# PROC010B_LP_Connector.net
KiCad netlist of a schematic drawn in Altium Designer
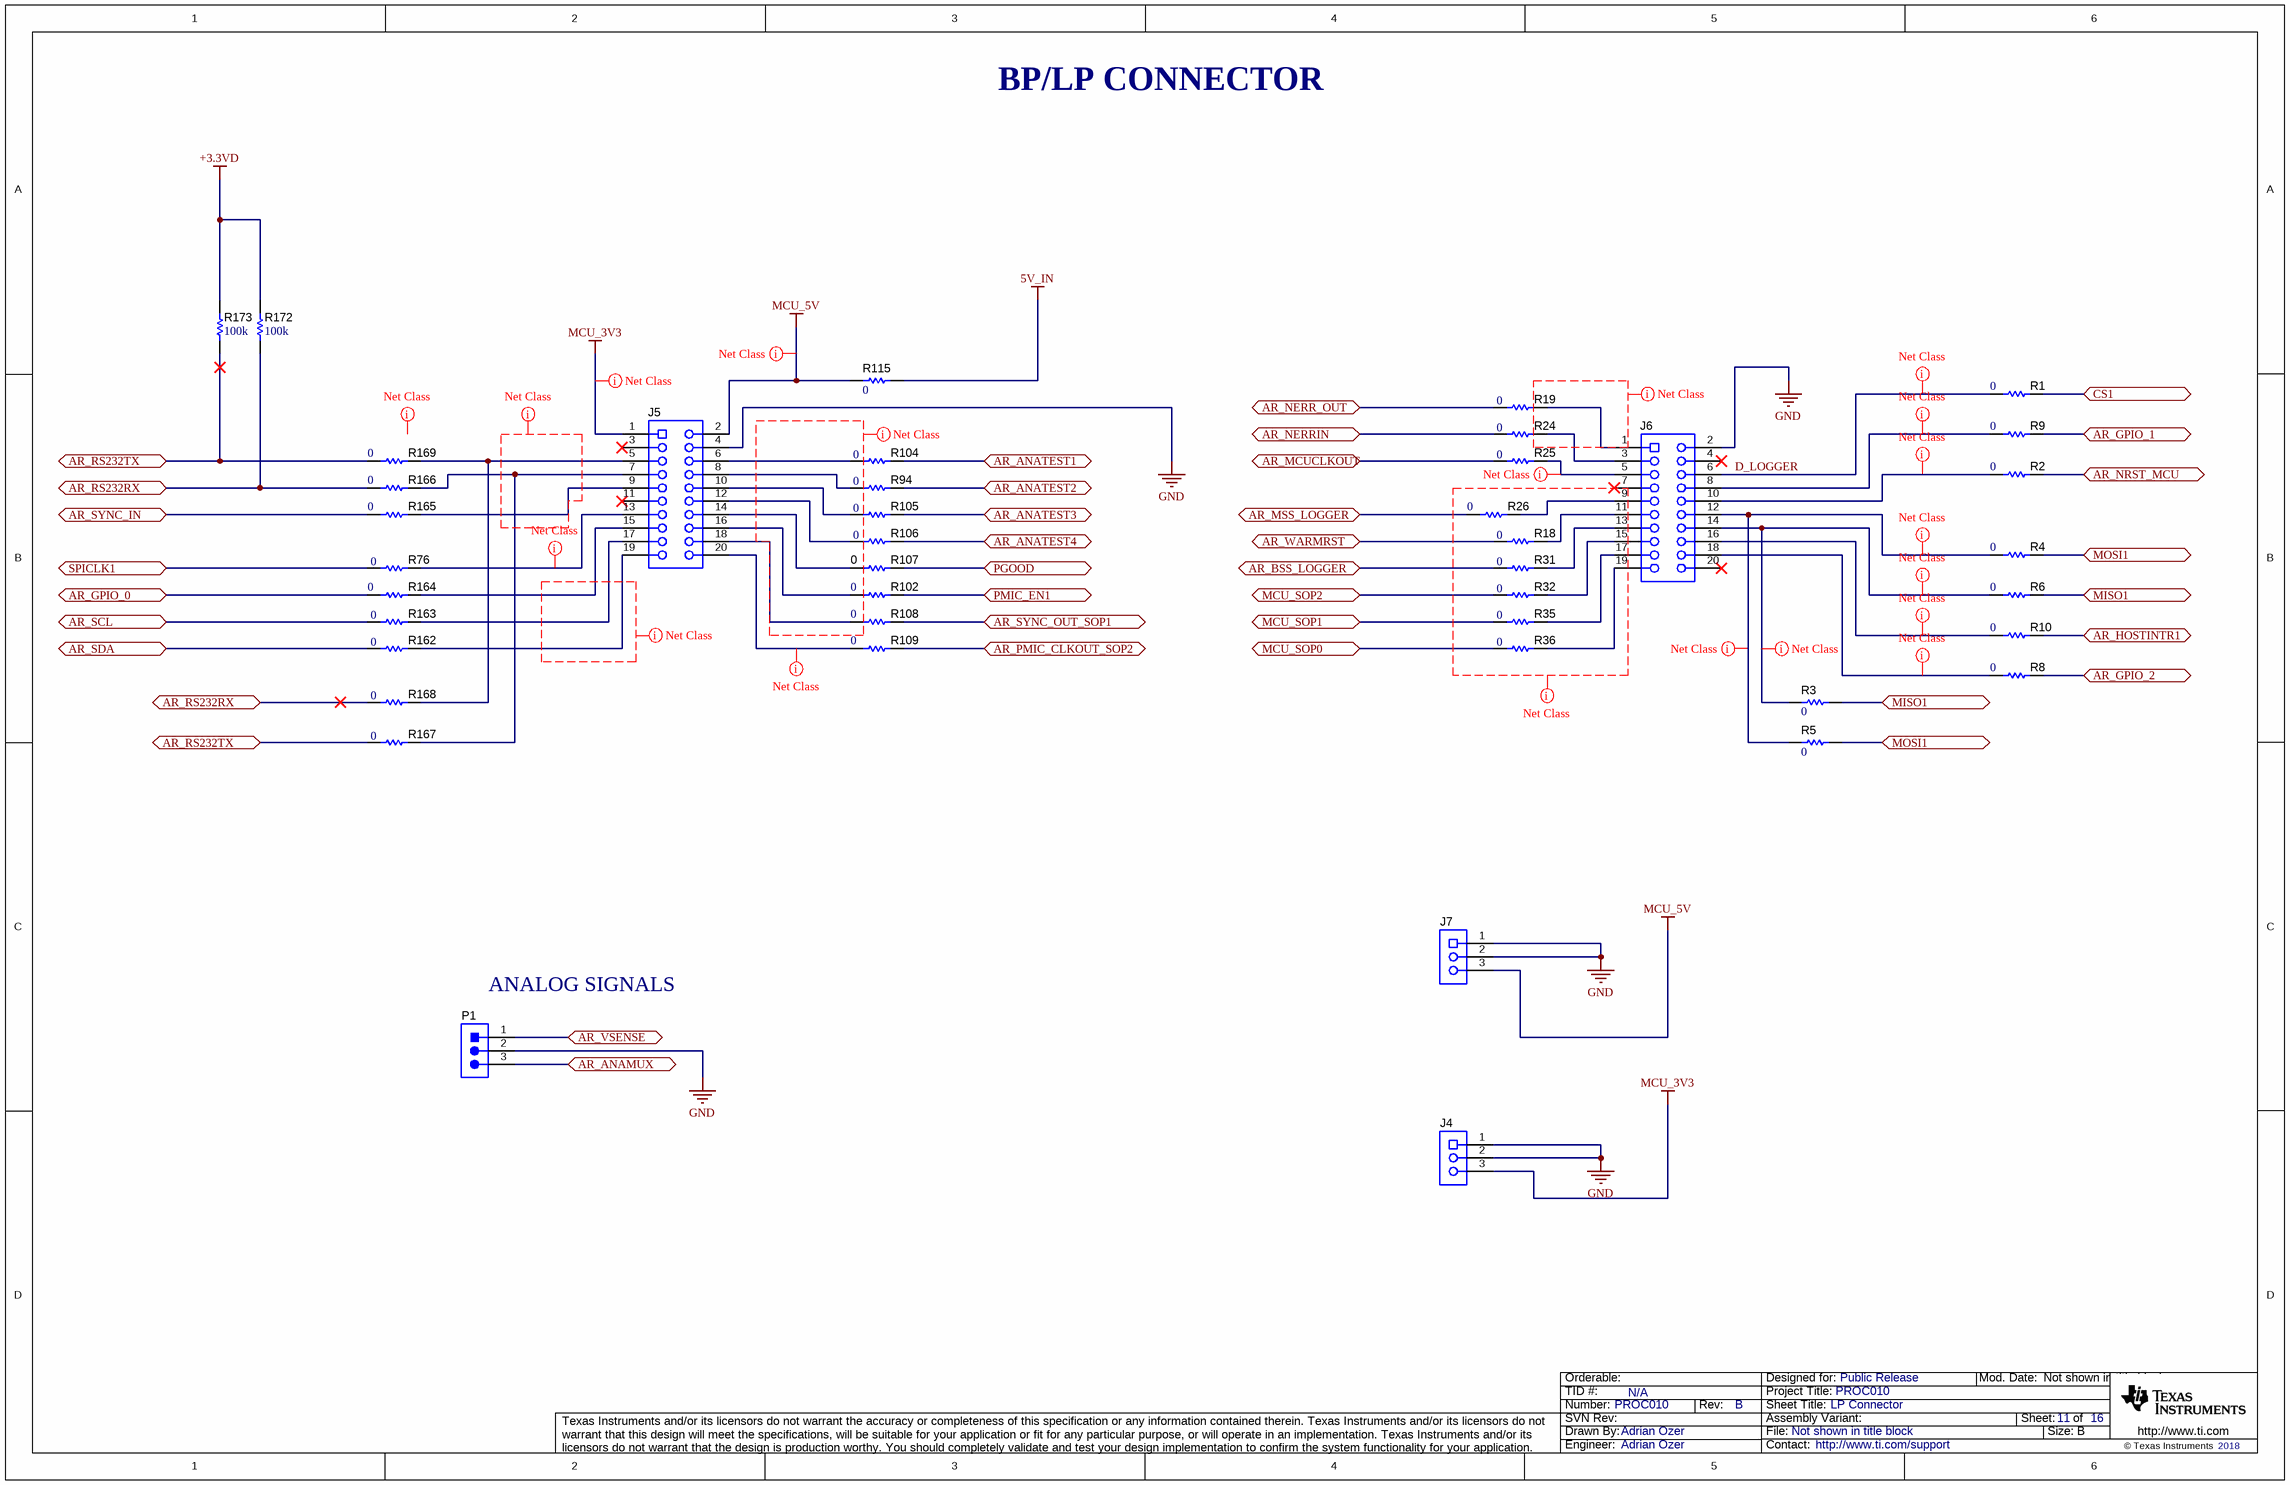
[diagram p0: PROC010B_LP Connector.SchDoc]

(export (version "E")
  (design (tool "Eeschema 10.0.6"))
  (components
    (comp (ref "J4")
      (value "SSM-103-S-SV")
      (footprint "Samtec_SSM-103-x-SV")
      (description "Receptacle, 2.54mm, 3x1, Gold with Tin tail, SMT")
      (fields (field (name "MANUFACTURER") "Samtec"))
      (libsource (lib "Altium Vault - TI") (part "CMP-0078183-1"))
    )
    (comp (ref "J5")
      (value "SSM-110-S-DV")
      (footprint "Samtec_SSM-110-x-DV")
      (description "Receptacle, 2.54mm, 10x2, Gold with Tin tail, SMT")
      (fields (field (name "MANUFACTURER") "Samtec"))
      (libsource (lib "Altium Vault - TI") (part "CMP-0078182-1"))
    )
    (comp (ref "J6")
      (value "SSM-110-S-DV")
      (footprint "Samtec_SSM-110-x-DV")
      (description "Receptacle, 2.54mm, 10x2, Gold with Tin tail, SMT")
      (fields (field (name "MANUFACTURER") "Samtec"))
      (libsource (lib "Altium Vault - TI") (part "CMP-0078182-1"))
    )
    (comp (ref "J7")
      (value "SSM-103-S-SV")
      (footprint "Samtec_SSM-103-x-SV")
      (description "Receptacle, 2.54mm, 3x1, Gold with Tin tail, SMT")
      (fields (field (name "MANUFACTURER") "Samtec"))
      (libsource (lib "Altium Vault - TI") (part "CMP-0078183-1"))
    )
    (comp (ref "P1")
      (value "TSW-103-07-T-S")
      (footprint "Samtec_TSW-103-07-T-S")
      (description "Header, 2.54 mm, 3x1, Tin, TH")
      (fields (field (name "MANUFACTURER") "Samtec"))
      (libsource (lib "Altium Vault - TI") (part "Header_3x1"))
    )
    (comp (ref "R1")
      (value "CRCW02010000Z0ED")
      (footprint "0201_Silk")
      (description "RES, 0, 5%, 0.05 W, 0201")
      (fields (field (name "MANUFACTURER") "Vishay-Dale") (field (name "VALUEDISPLAYED") "0"))
      (libsource (lib "Altium Vault - TI") (part "Resistor"))
    )
    (comp (ref "R2")
      (value "CRCW02010000Z0ED")
      (footprint "0201_Silk")
      (description "RES, 0, 5%, 0.05 W, 0201")
      (fields (field (name "MANUFACTURER") "Vishay-Dale") (field (name "VALUEDISPLAYED") "0"))
      (libsource (lib "Altium Vault - TI") (part "Resistor"))
    )
    (comp (ref "R3")
      (value "CRCW02010000Z0ED")
      (footprint "0201_Silk")
      (description "RES, 0, 5%, 0.05 W, 0201")
      (fields (field (name "MANUFACTURER") "Vishay-Dale") (field (name "VALUEDISPLAYED") "0"))
      (libsource (lib "Altium Vault - TI") (part "Resistor"))
    )
    (comp (ref "R4")
      (value "CRCW02010000Z0ED")
      (footprint "0201_Silk")
      (description "RES, 0, 5%, 0.05 W, 0201")
      (fields (field (name "MANUFACTURER") "Vishay-Dale") (field (name "VALUEDISPLAYED") "0"))
      (libsource (lib "Altium Vault - TI") (part "Resistor"))
    )
    (comp (ref "R5")
      (value "CRCW02010000Z0ED")
      (footprint "0201_Silk")
      (description "RES, 0, 5%, 0.05 W, 0201")
      (fields (field (name "MANUFACTURER") "Vishay-Dale") (field (name "VALUEDISPLAYED") "0"))
      (libsource (lib "Altium Vault - TI") (part "Resistor"))
    )
    (comp (ref "R6")
      (value "CRCW02010000Z0ED")
      (footprint "0201_Silk")
      (description "RES, 0, 5%, 0.05 W, 0201")
      (fields (field (name "MANUFACTURER") "Vishay-Dale") (field (name "VALUEDISPLAYED") "0"))
      (libsource (lib "Altium Vault - TI") (part "Resistor"))
    )
    (comp (ref "R8")
      (value "CRCW02010000Z0ED")
      (footprint "0201_Silk")
      (description "RES, 0, 5%, 0.05 W, 0201")
      (fields (field (name "MANUFACTURER") "Vishay-Dale") (field (name "VALUEDISPLAYED") "0"))
      (libsource (lib "Altium Vault - TI") (part "Resistor"))
    )
    (comp (ref "R9")
      (value "CRCW02010000Z0ED")
      (footprint "0201_Silk")
      (description "RES, 0, 5%, 0.05 W, 0201")
      (fields (field (name "MANUFACTURER") "Vishay-Dale") (field (name "VALUEDISPLAYED") "0"))
      (libsource (lib "Altium Vault - TI") (part "Resistor"))
    )
    (comp (ref "R10")
      (value "CRCW02010000Z0ED")
      (footprint "0201_Silk")
      (description "RES, 0, 5%, 0.05 W, 0201")
      (fields (field (name "MANUFACTURER") "Vishay-Dale") (field (name "VALUEDISPLAYED") "0"))
      (libsource (lib "Altium Vault - TI") (part "Resistor"))
    )
    (comp (ref "R18")
      (value "CRCW02010000Z0ED")
      (footprint "0201_Silk")
      (description "RES, 0, 5%, 0.05 W, 0201")
      (fields (field (name "MANUFACTURER") "Vishay-Dale") (field (name "VALUEDISPLAYED") "0"))
      (libsource (lib "Altium Vault - TI") (part "Resistor"))
    )
    (comp (ref "R19")
      (value "CRCW02010000Z0ED")
      (footprint "0201_Silk")
      (description "RES, 0, 5%, 0.05 W, 0201")
      (fields (field (name "MANUFACTURER") "Vishay-Dale") (field (name "VALUEDISPLAYED") "0"))
      (libsource (lib "Altium Vault - TI") (part "Resistor"))
    )
    (comp (ref "R24")
      (value "CRCW02010000Z0ED")
      (footprint "0201_Silk")
      (description "RES, 0, 5%, 0.05 W, 0201")
      (fields (field (name "MANUFACTURER") "Vishay-Dale") (field (name "VALUEDISPLAYED") "0"))
      (libsource (lib "Altium Vault - TI") (part "Resistor"))
    )
    (comp (ref "R25")
      (value "CRCW02010000Z0ED")
      (footprint "0201_Silk")
      (description "RES, 0, 5%, 0.05 W, 0201")
      (fields (field (name "MANUFACTURER") "Vishay-Dale") (field (name "VALUEDISPLAYED") "0"))
      (libsource (lib "Altium Vault - TI") (part "Resistor"))
    )
    (comp (ref "R26")
      (value "CRCW02010000Z0ED")
      (footprint "0201_Silk")
      (description "RES, 0, 5%, 0.05 W, 0201")
      (fields (field (name "MANUFACTURER") "Vishay-Dale") (field (name "VALUEDISPLAYED") "0"))
      (libsource (lib "Altium Vault - TI") (part "Resistor"))
    )
    (comp (ref "R31")
      (value "CRCW02010000Z0ED")
      (footprint "0201_Silk")
      (description "RES, 0, 5%, 0.05 W, 0201")
      (fields (field (name "MANUFACTURER") "Vishay-Dale") (field (name "VALUEDISPLAYED") "0"))
      (libsource (lib "Altium Vault - TI") (part "Resistor"))
    )
    (comp (ref "R32")
      (value "CRCW02010000Z0ED")
      (footprint "0201_Silk")
      (description "RES, 0, 5%, 0.05 W, 0201")
      (fields (field (name "MANUFACTURER") "Vishay-Dale") (field (name "VALUEDISPLAYED") "0"))
      (libsource (lib "Altium Vault - TI") (part "Resistor"))
    )
    (comp (ref "R35")
      (value "CRCW02010000Z0ED")
      (footprint "0201_Silk")
      (description "RES, 0, 5%, 0.05 W, 0201")
      (fields (field (name "MANUFACTURER") "Vishay-Dale") (field (name "VALUEDISPLAYED") "0"))
      (libsource (lib "Altium Vault - TI") (part "Resistor"))
    )
    (comp (ref "R36")
      (value "CRCW02010000Z0ED")
      (footprint "0201_Silk")
      (description "RES, 0, 5%, 0.05 W, 0201")
      (fields (field (name "MANUFACTURER") "Vishay-Dale") (field (name "VALUEDISPLAYED") "0"))
      (libsource (lib "Altium Vault - TI") (part "Resistor"))
    )
    (comp (ref "R76")
      (value "CRCW02010000Z0ED")
      (footprint "0201_Silk")
      (description "RES, 0, 5%, 0.05 W, 0201")
      (fields (field (name "MANUFACTURER") "Vishay-Dale") (field (name "VALUEDISPLAYED") "0"))
      (libsource (lib "Altium Vault - TI") (part "CMP-0027008-4"))
    )
    (comp (ref "R94")
      (value "CRCW02010000Z0ED")
      (footprint "0201_Silk")
      (description "RES, 0, 5%, 0.05 W, 0201")
      (fields (field (name "MANUFACTURER") "Vishay-Dale") (field (name "VALUEDISPLAYED") "0"))
      (libsource (lib "Altium Vault - TI") (part "Resistor"))
    )
    (comp (ref "R102")
      (value "CRCW02010000Z0ED")
      (footprint "0201_Silk")
      (description "RES, 0, 5%, 0.05 W, 0201")
      (fields (field (name "MANUFACTURER") "Vishay-Dale") (field (name "VALUEDISPLAYED") "0"))
      (libsource (lib "Altium Vault - TI") (part "Resistor"))
    )
    (comp (ref "R104")
      (value "CRCW02010000Z0ED")
      (footprint "0201_Silk")
      (description "RES, 0, 5%, 0.05 W, 0201")
      (fields (field (name "MANUFACTURER") "Vishay-Dale") (field (name "VALUEDISPLAYED") "0"))
      (libsource (lib "Altium Vault - TI") (part "CMP-0027008-4"))
    )
    (comp (ref "R105")
      (value "CRCW02010000Z0ED")
      (footprint "0201_Silk")
      (description "RES, 0, 5%, 0.05 W, 0201")
      (fields (field (name "MANUFACTURER") "Vishay-Dale") (field (name "VALUEDISPLAYED") "0"))
      (libsource (lib "Altium Vault - TI") (part "Resistor"))
    )
    (comp (ref "R106")
      (value "CRCW02010000Z0ED")
      (footprint "0201_Silk")
      (description "RES, 0, 5%, 0.05 W, 0201")
      (fields (field (name "MANUFACTURER") "Vishay-Dale") (field (name "VALUEDISPLAYED") "0"))
      (libsource (lib "Altium Vault - TI") (part "Resistor"))
    )
    (comp (ref "R107")
      (value "ERJ-2GE0R00X")
      (footprint "0402L")
      (description "RES, 0, 5%, 0.063 W, 0402")
      (fields
        (field (name "MANUFACTURER") "Panasonic")
        (field (name "VALUEDISPLAYED") "0")
        (field (name "PUBLISHER") "Texas Instruments")
      )
      (libsource (lib "Altium Vault - TI") (part "Resistor"))
    )
    (comp (ref "R108")
      (value "CRCW02010000Z0ED")
      (footprint "0201_Silk")
      (description "RES, 0, 5%, 0.05 W, 0201")
      (fields (field (name "MANUFACTURER") "Vishay-Dale") (field (name "VALUEDISPLAYED") "0"))
      (libsource (lib "Altium Vault - TI") (part "Resistor"))
    )
    (comp (ref "R109")
      (value "CRCW02010000Z0ED")
      (footprint "0201_Silk")
      (description "RES, 0, 5%, 0.05 W, 0201")
      (fields (field (name "MANUFACTURER") "Vishay-Dale") (field (name "VALUEDISPLAYED") "0"))
      (libsource (lib "Altium Vault - TI") (part "Resistor"))
    )
    (comp (ref "R115")
      (value "CRCW20100000Z0EF")
      (footprint "2010")
      (description "RES, 0, 5%, 0.75 W, AEC-Q200 Grade 0, 2010")
      (fields (field (name "MANUFACTURER") "Vishay-Dale") (field (name "VALUEDISPLAYED") "0"))
      (libsource (lib "Altium Vault - TI") (part "Resistor"))
    )
    (comp (ref "R162")
      (value "CRCW02010000Z0ED")
      (footprint "0201_Silk")
      (description "RES, 0, 5%, 0.05 W, 0201")
      (fields (field (name "MANUFACTURER") "Vishay-Dale") (field (name "VALUEDISPLAYED") "0"))
      (libsource (lib "Altium Vault - TI") (part "Resistor"))
    )
    (comp (ref "R163")
      (value "CRCW02010000Z0ED")
      (footprint "0201_Silk")
      (description "RES, 0, 5%, 0.05 W, 0201")
      (fields (field (name "MANUFACTURER") "Vishay-Dale") (field (name "VALUEDISPLAYED") "0"))
      (libsource (lib "Altium Vault - TI") (part "Resistor"))
    )
    (comp (ref "R164")
      (value "CRCW02010000Z0ED")
      (footprint "0201_Silk")
      (description "RES, 0, 5%, 0.05 W, 0201")
      (fields (field (name "MANUFACTURER") "Vishay-Dale") (field (name "VALUEDISPLAYED") "0"))
      (libsource (lib "Altium Vault - TI") (part "Resistor"))
    )
    (comp (ref "R165")
      (value "CRCW02010000Z0ED")
      (footprint "0201_Silk")
      (description "RES, 0, 5%, 0.05 W, 0201")
      (fields (field (name "MANUFACTURER") "Vishay-Dale") (field (name "VALUEDISPLAYED") "0"))
      (libsource (lib "Altium Vault - TI") (part "Resistor"))
    )
    (comp (ref "R166")
      (value "CRCW02010000Z0ED")
      (footprint "0201_Silk")
      (description "RES, 0, 5%, 0.05 W, 0201")
      (fields (field (name "MANUFACTURER") "Vishay-Dale") (field (name "VALUEDISPLAYED") "0"))
      (libsource (lib "Altium Vault - TI") (part "Resistor"))
    )
    (comp (ref "R167")
      (value "CRCW02010000Z0ED")
      (footprint "0201_Silk")
      (description "RES, 0, 5%, 0.05 W, 0201")
      (fields (field (name "MANUFACTURER") "Vishay-Dale") (field (name "VALUEDISPLAYED") "0"))
      (libsource (lib "Altium Vault - TI") (part "Resistor"))
    )
    (comp (ref "R168")
      (value "CRCW02010000Z0ED")
      (footprint "0201_Silk")
      (description "RES, 0, 5%, 0.05 W, 0201")
      (fields (field (name "MANUFACTURER") "Vishay-Dale") (field (name "VALUEDISPLAYED") "0"))
      (libsource (lib "Altium Vault - TI") (part "Resistor"))
    )
    (comp (ref "R169")
      (value "CRCW02010000Z0ED")
      (footprint "0201_Silk")
      (description "RES, 0, 5%, 0.05 W, 0201")
      (fields (field (name "MANUFACTURER") "Vishay-Dale") (field (name "VALUEDISPLAYED") "0"))
      (libsource (lib "Altium Vault - TI") (part "Resistor"))
    )
    (comp (ref "R172")
      (value "CRCW0402100KFKED")
      (footprint "0402L")
      (description "RES, 100 k, 1%, 0.063 W, AEC-Q200 Grade 0, 0402")
      (fields (field (name "MANUFACTURER") "Vishay-Dale") (field (name "VALUEDISPLAYED") "100k"))
      (libsource (lib "Altium Vault - TI") (part "Resistor"))
    )
    (comp (ref "R173")
      (value "CRCW0402100KFKED")
      (footprint "0402L")
      (description "RES, 100 k, 1%, 0.063 W, AEC-Q200 Grade 0, 0402")
      (fields (field (name "MANUFACTURER") "Vishay-Dale") (field (name "VALUEDISPLAYED") "100k"))
      (libsource (lib "Altium Vault - TI") (part "Resistor"))
    )
  )
  (nets
    (net (code "1") (name "+3.3VD") (class "Default")
      (node (ref "R172") (pin "2") (pinfunction "2_2") (pintype "passive"))
      (node (ref "R173") (pin "2") (pinfunction "2_2") (pintype "passive"))
    )
    (net (code "2") (name "/AR_ANAMUX") (class "Default")
      (node (ref "P1") (pin "3") (pinfunction "3_3") (pintype "passive"))
    )
    (net (code "3") (name "/AR_ANATEST1") (class "Default")
      (node (ref "R104") (pin "2") (pinfunction "2_2") (pintype "passive"))
    )
    (net (code "4") (name "/AR_ANATEST2") (class "Default")
      (node (ref "R94") (pin "2") (pinfunction "2_2") (pintype "passive"))
    )
    (net (code "5") (name "/AR_ANATEST3") (class "Default")
      (node (ref "R105") (pin "2") (pinfunction "2_2") (pintype "passive"))
    )
    (net (code "6") (name "/AR_ANATEST4") (class "Default")
      (node (ref "R106") (pin "2") (pinfunction "2_2") (pintype "passive"))
    )
    (net (code "7") (name "/AR_BSS_LOGGER") (class "Default")
      (node (ref "R31") (pin "1") (pinfunction "1_1") (pintype "passive"))
    )
    (net (code "8") (name "/AR_GPIO_0") (class "Default")
      (node (ref "R164") (pin "1") (pinfunction "1_1") (pintype "passive"))
    )
    (net (code "9") (name "/AR_GPIO_1") (class "Default")
      (node (ref "R9") (pin "2") (pinfunction "2_2") (pintype "passive"))
    )
    (net (code "10") (name "/AR_GPIO_2") (class "Default")
      (node (ref "R8") (pin "2") (pinfunction "2_2") (pintype "passive"))
    )
    (net (code "11") (name "/AR_HOSTINTR1") (class "Default")
      (node (ref "R10") (pin "2") (pinfunction "2_2") (pintype "passive"))
    )
    (net (code "12") (name "/AR_MCUCLKOUT") (class "Default")
      (node (ref "R25") (pin "1") (pinfunction "1_1") (pintype "passive"))
    )
    (net (code "13") (name "/AR_MSS_LOGGER") (class "Default")
      (node (ref "R26") (pin "1") (pinfunction "1_1") (pintype "passive"))
    )
    (net (code "14") (name "/AR_NERRIN") (class "Default")
      (node (ref "R24") (pin "1") (pinfunction "1_1") (pintype "passive"))
    )
    (net (code "15") (name "/AR_NERR_OUT") (class "Default")
      (node (ref "R19") (pin "1") (pinfunction "1_1") (pintype "passive"))
    )
    (net (code "16") (name "/AR_NRST_MCU") (class "Default")
      (node (ref "R2") (pin "2") (pinfunction "2_2") (pintype "passive"))
    )
    (net (code "17") (name "/AR_PMIC_CLKOUT_SOP2") (class "Default")
      (node (ref "R109") (pin "2") (pinfunction "2_2") (pintype "passive"))
    )
    (net (code "18") (name "/AR_RS232RX") (class "Default")
      (node (ref "R166") (pin "1") (pinfunction "1_1") (pintype "passive"))
      (node (ref "R168") (pin "1") (pinfunction "1_1") (pintype "passive"))
      (node (ref "R172") (pin "1") (pinfunction "1_1") (pintype "passive"))
    )
    (net (code "19") (name "/AR_RS232TX") (class "Default")
      (node (ref "R167") (pin "1") (pinfunction "1_1") (pintype "passive"))
      (node (ref "R169") (pin "1") (pinfunction "1_1") (pintype "passive"))
      (node (ref "R173") (pin "1") (pinfunction "1_1") (pintype "passive"))
    )
    (net (code "20") (name "/AR_SCL") (class "Default")
      (node (ref "R163") (pin "1") (pinfunction "1_1") (pintype "passive"))
    )
    (net (code "21") (name "/AR_SDA") (class "Default")
      (node (ref "R162") (pin "1") (pinfunction "1_1") (pintype "passive"))
    )
    (net (code "22") (name "/AR_SYNC_IN") (class "Default")
      (node (ref "R165") (pin "1") (pinfunction "1_1") (pintype "passive"))
    )
    (net (code "23") (name "/AR_SYNC_OUT_SOP1") (class "Default")
      (node (ref "R108") (pin "2") (pinfunction "2_2") (pintype "passive"))
    )
    (net (code "24") (name "/AR_VSENSE") (class "Default")
      (node (ref "P1") (pin "1") (pinfunction "1_1") (pintype "passive"))
    )
    (net (code "25") (name "/AR_WARMRST") (class "Default")
      (node (ref "R18") (pin "1") (pinfunction "1_1") (pintype "passive"))
    )
    (net (code "26") (name "/CS1") (class "Default")
      (node (ref "R1") (pin "2") (pinfunction "2_2") (pintype "passive"))
    )
    (net (code "27") (name "/D_LOGGER") (class "Default")
      (node (ref "J6") (pin "6") (pinfunction "6_6") (pintype "passive"))
      (node (ref "R1") (pin "1") (pinfunction "1_1") (pintype "passive"))
    )
    (net (code "28") (name "/MCU_SOP0") (class "Default")
      (node (ref "R36") (pin "1") (pinfunction "1_1") (pintype "passive"))
    )
    (net (code "29") (name "/MCU_SOP1") (class "Default")
      (node (ref "R35") (pin "1") (pinfunction "1_1") (pintype "passive"))
    )
    (net (code "30") (name "/MCU_SOP2") (class "Default")
      (node (ref "R32") (pin "1") (pinfunction "1_1") (pintype "passive"))
    )
    (net (code "31") (name "/MISO1") (class "Default")
      (node (ref "R3") (pin "2") (pinfunction "2_2") (pintype "passive"))
      (node (ref "R6") (pin "2") (pinfunction "2_2") (pintype "passive"))
    )
    (net (code "32") (name "/MOSI1") (class "Default")
      (node (ref "R4") (pin "2") (pinfunction "2_2") (pintype "passive"))
      (node (ref "R5") (pin "2") (pinfunction "2_2") (pintype "passive"))
    )
    (net (code "33") (name "/PGOOD") (class "Default")
      (node (ref "R107") (pin "2") (pinfunction "2_2") (pintype "passive"))
    )
    (net (code "34") (name "/PMIC_EN1") (class "Default")
      (node (ref "R102") (pin "2") (pinfunction "2_2") (pintype "passive"))
    )
    (net (code "35") (name "/SPICLK1") (class "Default")
      (node (ref "R76") (pin "1") (pinfunction "1_1") (pintype "passive"))
    )
    (net (code "36") (name "5V_IN") (class "Default")
      (node (ref "R115") (pin "2") (pinfunction "2_2") (pintype "passive"))
    )
    (net (code "37") (name "GND") (class "Default")
      (node (ref "J4") (pin "1") (pinfunction "1_1") (pintype "passive"))
      (node (ref "J4") (pin "2") (pinfunction "2_2") (pintype "passive"))
      (node (ref "J5") (pin "4") (pinfunction "4_4") (pintype "passive"))
      (node (ref "J6") (pin "2") (pinfunction "2_2") (pintype "passive"))
      (node (ref "J7") (pin "1") (pinfunction "1_1") (pintype "passive"))
      (node (ref "J7") (pin "2") (pinfunction "2_2") (pintype "passive"))
      (node (ref "P1") (pin "2") (pinfunction "2_2") (pintype "passive"))
    )
    (net (code "38") (name "MCU_3V3") (class "Default")
      (node (ref "J4") (pin "3") (pinfunction "3_3") (pintype "passive"))
      (node (ref "J5") (pin "1") (pinfunction "1_1") (pintype "passive"))
    )
    (net (code "39") (name "MCU_5V") (class "Default")
      (node (ref "J5") (pin "2") (pinfunction "2_2") (pintype "passive"))
      (node (ref "J7") (pin "3") (pinfunction "3_3") (pintype "passive"))
      (node (ref "R115") (pin "1") (pinfunction "1_1") (pintype "passive"))
    )
    (net (code "40") (name "Net-(J5-Pad5)") (class "Default")
      (node (ref "J5") (pin "5") (pinfunction "5_5") (pintype "passive"))
      (node (ref "R168") (pin "2") (pinfunction "2_2") (pintype "passive"))
      (node (ref "R169") (pin "2") (pinfunction "2_2") (pintype "passive"))
    )
    (net (code "41") (name "Net-(J5-Pad6)") (class "Default")
      (node (ref "J5") (pin "6") (pinfunction "6_6") (pintype "passive"))
      (node (ref "R104") (pin "1") (pinfunction "1_1") (pintype "passive"))
    )
    (net (code "42") (name "Net-(J5-Pad7)") (class "Default")
      (node (ref "J5") (pin "7") (pinfunction "7_7") (pintype "passive"))
      (node (ref "R166") (pin "2") (pinfunction "2_2") (pintype "passive"))
      (node (ref "R167") (pin "2") (pinfunction "2_2") (pintype "passive"))
    )
    (net (code "43") (name "Net-(J5-Pad8)") (class "Default")
      (node (ref "J5") (pin "8") (pinfunction "8_8") (pintype "passive"))
      (node (ref "R94") (pin "1") (pinfunction "1_1") (pintype "passive"))
    )
    (net (code "44") (name "Net-(J5-Pad9)") (class "Default")
      (node (ref "J5") (pin "9") (pinfunction "9_9") (pintype "passive"))
      (node (ref "R165") (pin "2") (pinfunction "2_2") (pintype "passive"))
    )
    (net (code "45") (name "Net-(J5-Pad10)") (class "Default")
      (node (ref "J5") (pin "10") (pinfunction "10_10") (pintype "passive"))
      (node (ref "R105") (pin "1") (pinfunction "1_1") (pintype "passive"))
    )
    (net (code "46") (name "Net-(J5-Pad12)") (class "Default")
      (node (ref "J5") (pin "12") (pinfunction "12_12") (pintype "passive"))
      (node (ref "R106") (pin "1") (pinfunction "1_1") (pintype "passive"))
    )
    (net (code "47") (name "Net-(J5-Pad13)") (class "Default")
      (node (ref "J5") (pin "13") (pinfunction "13_13") (pintype "passive"))
      (node (ref "R76") (pin "2") (pinfunction "2_2") (pintype "passive"))
    )
    (net (code "48") (name "Net-(J5-Pad14)") (class "Default")
      (node (ref "J5") (pin "14") (pinfunction "14_14") (pintype "passive"))
      (node (ref "R107") (pin "1") (pinfunction "1_1") (pintype "passive"))
    )
    (net (code "49") (name "Net-(J5-Pad15)") (class "Default")
      (node (ref "J5") (pin "15") (pinfunction "15_15") (pintype "passive"))
      (node (ref "R164") (pin "2") (pinfunction "2_2") (pintype "passive"))
    )
    (net (code "50") (name "Net-(J5-Pad16)") (class "Default")
      (node (ref "J5") (pin "16") (pinfunction "16_16") (pintype "passive"))
      (node (ref "R102") (pin "1") (pinfunction "1_1") (pintype "passive"))
    )
    (net (code "51") (name "Net-(J5-Pad17)") (class "Default")
      (node (ref "J5") (pin "17") (pinfunction "17_17") (pintype "passive"))
      (node (ref "R163") (pin "2") (pinfunction "2_2") (pintype "passive"))
    )
    (net (code "52") (name "Net-(J5-Pad18)") (class "Default")
      (node (ref "J5") (pin "18") (pinfunction "18_18") (pintype "passive"))
      (node (ref "R108") (pin "1") (pinfunction "1_1") (pintype "passive"))
    )
    (net (code "53") (name "Net-(J5-Pad19)") (class "Default")
      (node (ref "J5") (pin "19") (pinfunction "19_19") (pintype "passive"))
      (node (ref "R162") (pin "2") (pinfunction "2_2") (pintype "passive"))
    )
    (net (code "54") (name "Net-(J5-Pad20)") (class "Default")
      (node (ref "J5") (pin "20") (pinfunction "20_20") (pintype "passive"))
      (node (ref "R109") (pin "1") (pinfunction "1_1") (pintype "passive"))
    )
    (net (code "55") (name "Net-(J6-Pad1)") (class "Default")
      (node (ref "J6") (pin "1") (pinfunction "1_1") (pintype "passive"))
      (node (ref "R19") (pin "2") (pinfunction "2_2") (pintype "passive"))
    )
    (net (code "56") (name "Net-(J6-Pad3)") (class "Default")
      (node (ref "J6") (pin "3") (pinfunction "3_3") (pintype "passive"))
      (node (ref "R24") (pin "2") (pinfunction "2_2") (pintype "passive"))
    )
    (net (code "57") (name "Net-(J6-Pad5)") (class "Default")
      (node (ref "J6") (pin "5") (pinfunction "5_5") (pintype "passive"))
      (node (ref "R25") (pin "2") (pinfunction "2_2") (pintype "passive"))
    )
    (net (code "58") (name "Net-(J6-Pad8)") (class "Default")
      (node (ref "J6") (pin "8") (pinfunction "8_8") (pintype "passive"))
      (node (ref "R9") (pin "1") (pinfunction "1_1") (pintype "passive"))
    )
    (net (code "59") (name "Net-(J6-Pad9)") (class "Default")
      (node (ref "J6") (pin "9") (pinfunction "9_9") (pintype "passive"))
      (node (ref "R26") (pin "2") (pinfunction "2_2") (pintype "passive"))
    )
    (net (code "60") (name "Net-(J6-Pad10)") (class "Default")
      (node (ref "J6") (pin "10") (pinfunction "10_10") (pintype "passive"))
      (node (ref "R2") (pin "1") (pinfunction "1_1") (pintype "passive"))
    )
    (net (code "61") (name "Net-(J6-Pad11)") (class "Default")
      (node (ref "J6") (pin "11") (pinfunction "11_11") (pintype "passive"))
      (node (ref "R18") (pin "2") (pinfunction "2_2") (pintype "passive"))
    )
    (net (code "62") (name "Net-(J6-Pad12)") (class "Default")
      (node (ref "J6") (pin "12") (pinfunction "12_12") (pintype "passive"))
      (node (ref "R4") (pin "1") (pinfunction "1_1") (pintype "passive"))
      (node (ref "R5") (pin "1") (pinfunction "1_1") (pintype "passive"))
    )
    (net (code "63") (name "Net-(J6-Pad13)") (class "Default")
      (node (ref "J6") (pin "13") (pinfunction "13_13") (pintype "passive"))
      (node (ref "R31") (pin "2") (pinfunction "2_2") (pintype "passive"))
    )
    (net (code "64") (name "Net-(J6-Pad14)") (class "Default")
      (node (ref "J6") (pin "14") (pinfunction "14_14") (pintype "passive"))
      (node (ref "R3") (pin "1") (pinfunction "1_1") (pintype "passive"))
      (node (ref "R6") (pin "1") (pinfunction "1_1") (pintype "passive"))
    )
    (net (code "65") (name "Net-(J6-Pad15)") (class "Default")
      (node (ref "J6") (pin "15") (pinfunction "15_15") (pintype "passive"))
      (node (ref "R32") (pin "2") (pinfunction "2_2") (pintype "passive"))
    )
    (net (code "66") (name "Net-(J6-Pad16)") (class "Default")
      (node (ref "J6") (pin "16") (pinfunction "16_16") (pintype "passive"))
      (node (ref "R10") (pin "1") (pinfunction "1_1") (pintype "passive"))
    )
    (net (code "67") (name "Net-(J6-Pad17)") (class "Default")
      (node (ref "J6") (pin "17") (pinfunction "17_17") (pintype "passive"))
      (node (ref "R35") (pin "2") (pinfunction "2_2") (pintype "passive"))
    )
    (net (code "68") (name "Net-(J6-Pad18)") (class "Default")
      (node (ref "J6") (pin "18") (pinfunction "18_18") (pintype "passive"))
      (node (ref "R8") (pin "1") (pinfunction "1_1") (pintype "passive"))
    )
    (net (code "69") (name "Net-(J6-Pad19)") (class "Default")
      (node (ref "J6") (pin "19") (pinfunction "19_19") (pintype "passive"))
      (node (ref "R36") (pin "2") (pinfunction "2_2") (pintype "passive"))
    )
    (net (code "70") (name "unconnected-(J5-Pad3)") (class "Default")
      (node (ref "J5") (pin "3") (pinfunction "3_3") (pintype "passive+no_connect"))
    )
    (net (code "71") (name "unconnected-(J5-Pad11)") (class "Default")
      (node (ref "J5") (pin "11") (pinfunction "11_11") (pintype "passive+no_connect"))
    )
    (net (code "72") (name "unconnected-(J6-Pad4)") (class "Default")
      (node (ref "J6") (pin "4") (pinfunction "4_4") (pintype "passive+no_connect"))
    )
    (net (code "73") (name "unconnected-(J6-Pad7)") (class "Default")
      (node (ref "J6") (pin "7") (pinfunction "7_7") (pintype "passive+no_connect"))
    )
    (net (code "74") (name "unconnected-(J6-Pad20)") (class "Default")
      (node (ref "J6") (pin "20") (pinfunction "20_20") (pintype "passive+no_connect"))
    )
  )
)
